# SoC_GPIO_3_3V.net
KiCad netlist of a schematic drawn in Altium Designer
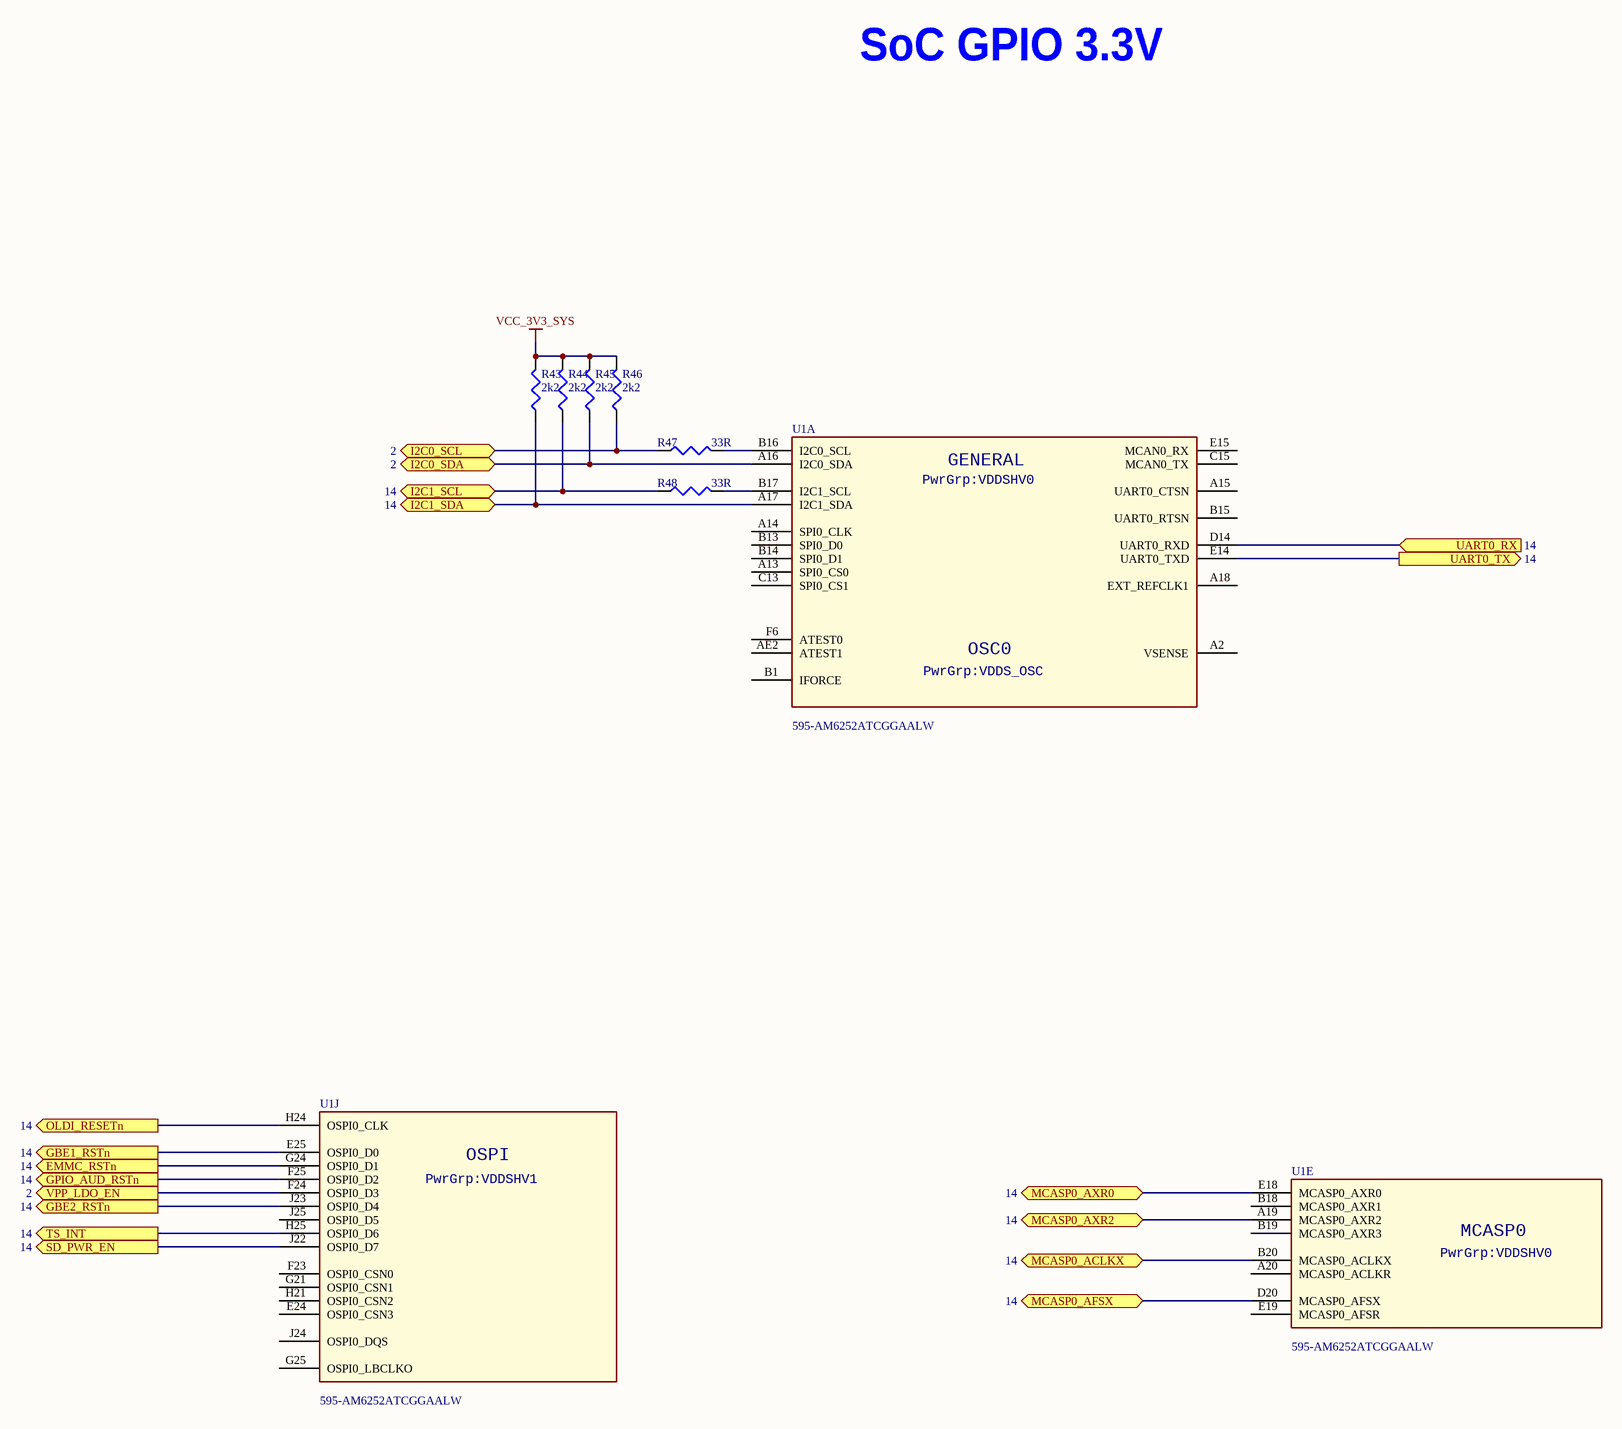
[diagram p0: SoC GPIO 3.3V.SchDoc]

(export (version "E")
  (design (tool "Eeschema 10.0.6"))
  (components
    (comp (ref "R43")
      (value "2k2")
      (footprint "R0402")
      (description "RES 2.20K OHM 1/16W 1% 0402 SMD")
      (fields
        (field (name "MANUFACTURER") "Yageo")
        (field (name "MANUFACTURER PART NUMBER") "RC0402FR-072K2L")
      )
      (libsource (lib "Schlib AM625") (part "RC0402FR-072K2L"))
    )
    (comp (ref "R44")
      (value "2k2")
      (footprint "R0402")
      (description "RES 2.20K OHM 1/16W 1% 0402 SMD")
      (fields
        (field (name "MANUFACTURER") "Yageo")
        (field (name "MANUFACTURER PART NUMBER") "RC0402FR-072K2L")
      )
      (libsource (lib "Schlib AM625") (part "RC0402FR-072K2L"))
    )
    (comp (ref "R45")
      (value "2k2")
      (footprint "R0402")
      (description "RES 2.20K OHM 1/16W 1% 0402 SMD")
      (fields
        (field (name "MANUFACTURER") "Yageo")
        (field (name "MANUFACTURER PART NUMBER") "RC0402FR-072K2L")
      )
      (libsource (lib "Schlib AM625") (part "RC0402FR-072K2L"))
    )
    (comp (ref "R46")
      (value "2k2")
      (footprint "R0402")
      (description "RES 2.20K OHM 1/16W 1% 0402 SMD")
      (fields
        (field (name "MANUFACTURER") "Yageo")
        (field (name "MANUFACTURER PART NUMBER") "RC0402FR-072K2L")
      )
      (libsource (lib "Schlib AM625") (part "RC0402FR-072K2L"))
    )
    (comp (ref "R47")
      (value "33R")
      (footprint "R0201")
      (description "RES 33 OHM 1% 1/20W 0201")
      (fields
        (field (name "MANUFACTURER") "Yageo")
        (field (name "MANUFACTURER PART NUMBER") "RC0201FR-0733RL")
      )
      (libsource (lib "Schlib AM625") (part "RC0201FR-0733RL"))
    )
    (comp (ref "R48")
      (value "33R")
      (footprint "R0201")
      (description "RES 33 OHM 1% 1/20W 0201")
      (fields
        (field (name "MANUFACTURER") "Yageo")
        (field (name "MANUFACTURER PART NUMBER") "RC0201FR-0733RL")
      )
      (libsource (lib "Schlib AM625") (part "RC0201FR-0733RL"))
    )
    (comp (ref "U1")
      (value "AM62-EVM_BGA425")
      (footprint "BGA425C50P25X25_1300X1300X89")
      (description "ARM® Cortex®-A53 Microprocessor IC Sitara™ 2 Core, 64-Bit 1.4GHz 425-FCCSP (13x13)")
      (fields
        (field (name "MANUFACTURER") "Texas Instruments")
        (field (name "MANUFACTURER PART NUMBER") "AM6252ATCGGAALW")
        (field (name "SUPPLIER PART NUMBER 1") "595-AM6252ATCGGAALW")
      )
      (libsource (lib "Schlib AM625") (part "AM62-EVM_BGA425"))
    )
  )
  (nets
    (net (code "1") (name "/EMMC_RSTn") (class "Default")
      (node (ref "U1") (pin "G24") (pinfunction "OSPI0_D1_G24") (pintype "passive"))
    )
    (net (code "2") (name "/GBE1_RSTn") (class "Default")
      (node (ref "U1") (pin "E25") (pinfunction "OSPI0_D0_E25") (pintype "passive"))
    )
    (net (code "3") (name "/GBE2_RSTn") (class "Default")
      (node (ref "U1") (pin "J23") (pinfunction "OSPI0_D4_J23") (pintype "passive"))
    )
    (net (code "4") (name "/GPIO_AUD_RSTn") (class "Default")
      (node (ref "U1") (pin "F25") (pinfunction "OSPI0_D2_F25") (pintype "passive"))
    )
    (net (code "5") (name "/I2C0_SCL") (class "Default")
      (node (ref "R46") (pin "1") (pinfunction "1_1") (pintype "passive"))
      (node (ref "R47") (pin "1") (pinfunction "1_1") (pintype "passive"))
    )
    (net (code "6") (name "/I2C0_SDA") (class "Default")
      (node (ref "R45") (pin "1") (pinfunction "1_1") (pintype "passive"))
      (node (ref "U1") (pin "A16") (pinfunction "I2C0_SDA_A16") (pintype "passive"))
    )
    (net (code "7") (name "/I2C1_SCL") (class "Default")
      (node (ref "R44") (pin "1") (pinfunction "1_1") (pintype "passive"))
      (node (ref "R48") (pin "1") (pinfunction "1_1") (pintype "passive"))
    )
    (net (code "8") (name "/I2C1_SDA") (class "Default")
      (node (ref "R43") (pin "1") (pinfunction "1_1") (pintype "passive"))
      (node (ref "U1") (pin "A17") (pinfunction "I2C1_SDA_A17") (pintype "passive"))
    )
    (net (code "9") (name "/MCASP0_ACLKX") (class "Default")
      (node (ref "U1") (pin "B20") (pinfunction "MCASP0_ACLKX_B20") (pintype "passive"))
    )
    (net (code "10") (name "/MCASP0_AFSX") (class "Default")
      (node (ref "U1") (pin "D20") (pinfunction "MCASP0_AFSX_D20") (pintype "passive"))
    )
    (net (code "11") (name "/MCASP0_AXR0") (class "Default")
      (node (ref "U1") (pin "E18") (pinfunction "MCASP0_AXR0_E18") (pintype "passive"))
    )
    (net (code "12") (name "/MCASP0_AXR2") (class "Default")
      (node (ref "U1") (pin "A19") (pinfunction "MCASP0_AXR2_A19") (pintype "passive"))
    )
    (net (code "13") (name "/OLDI_RESETn") (class "Default")
      (node (ref "U1") (pin "H24") (pinfunction "OSPI0_CLK_H24") (pintype "passive"))
    )
    (net (code "14") (name "/SD_PWR_EN") (class "Default")
      (node (ref "U1") (pin "J22") (pinfunction "OSPI0_D7_J22") (pintype "passive"))
    )
    (net (code "15") (name "/TS_INT") (class "Default")
      (node (ref "U1") (pin "H25") (pinfunction "OSPI0_D6_H25") (pintype "passive"))
    )
    (net (code "16") (name "/UART0_RX") (class "Default")
      (node (ref "U1") (pin "D14") (pinfunction "UART0_RXD_D14") (pintype "passive"))
    )
    (net (code "17") (name "/UART0_TX") (class "Default")
      (node (ref "U1") (pin "E14") (pinfunction "UART0_TXD_E14") (pintype "passive"))
    )
    (net (code "18") (name "/VPP_LDO_EN") (class "Default")
      (node (ref "U1") (pin "F24") (pinfunction "OSPI0_D3_F24") (pintype "passive"))
    )
    (net (code "19") (name "Net-(U1A-I2C0_SCL)") (class "Default")
      (node (ref "R47") (pin "2") (pinfunction "2_2") (pintype "passive"))
      (node (ref "U1") (pin "B16") (pinfunction "I2C0_SCL_B16") (pintype "passive"))
    )
    (net (code "20") (name "Net-(U1A-I2C1_SCL)") (class "Default")
      (node (ref "R48") (pin "2") (pinfunction "2_2") (pintype "passive"))
      (node (ref "U1") (pin "B17") (pinfunction "I2C1_SCL_B17") (pintype "passive"))
    )
    (net (code "21") (name "VCC_3V3_SYS") (class "Default")
      (node (ref "R43") (pin "2") (pinfunction "2_2") (pintype "passive"))
      (node (ref "R44") (pin "2") (pinfunction "2_2") (pintype "passive"))
      (node (ref "R45") (pin "2") (pinfunction "2_2") (pintype "passive"))
      (node (ref "R46") (pin "2") (pinfunction "2_2") (pintype "passive"))
    )
    (net (code "22") (name "unconnected-(U1A-ATEST0-PadF6)") (class "Default")
      (node (ref "U1") (pin "F6") (pinfunction "ATEST0_F6") (pintype "passive"))
    )
    (net (code "23") (name "unconnected-(U1A-ATEST1-PadAE2)") (class "Default")
      (node (ref "U1") (pin "AE2") (pinfunction "ATEST1_AE2") (pintype "passive"))
    )
    (net (code "24") (name "unconnected-(U1A-EXT_REFCLK1-PadA18)") (class "Default")
      (node (ref "U1") (pin "A18") (pinfunction "EXT_REFCLK1_A18") (pintype "passive"))
    )
    (net (code "25") (name "unconnected-(U1A-IFORCE-PadB1)") (class "Default")
      (node (ref "U1") (pin "B1") (pinfunction "IFORCE_B1") (pintype "passive"))
    )
    (net (code "26") (name "unconnected-(U1A-MCAN0_RX-PadE15)") (class "Default")
      (node (ref "U1") (pin "E15") (pinfunction "MCAN0_RX_E15") (pintype "passive"))
    )
    (net (code "27") (name "unconnected-(U1A-MCAN0_TX-PadC15)") (class "Default")
      (node (ref "U1") (pin "C15") (pinfunction "MCAN0_TX_C15") (pintype "passive"))
    )
    (net (code "28") (name "unconnected-(U1A-SPI0_CLK-PadA14)") (class "Default")
      (node (ref "U1") (pin "A14") (pinfunction "SPI0_CLK_A14") (pintype "passive"))
    )
    (net (code "29") (name "unconnected-(U1A-SPI0_CS0-PadA13)") (class "Default")
      (node (ref "U1") (pin "A13") (pinfunction "SPI0_CS0_A13") (pintype "passive"))
    )
    (net (code "30") (name "unconnected-(U1A-SPI0_CS1-PadC13)") (class "Default")
      (node (ref "U1") (pin "C13") (pinfunction "SPI0_CS1_C13") (pintype "passive"))
    )
    (net (code "31") (name "unconnected-(U1A-SPI0_D0-PadB13)") (class "Default")
      (node (ref "U1") (pin "B13") (pinfunction "SPI0_D0_B13") (pintype "passive"))
    )
    (net (code "32") (name "unconnected-(U1A-SPI0_D1-PadB14)") (class "Default")
      (node (ref "U1") (pin "B14") (pinfunction "SPI0_D1_B14") (pintype "passive"))
    )
    (net (code "33") (name "unconnected-(U1A-UART0_CTSN-PadA15)") (class "Default")
      (node (ref "U1") (pin "A15") (pinfunction "UART0_CTSN_A15") (pintype "passive"))
    )
    (net (code "34") (name "unconnected-(U1A-UART0_RTSN-PadB15)") (class "Default")
      (node (ref "U1") (pin "B15") (pinfunction "UART0_RTSN_B15") (pintype "passive"))
    )
    (net (code "35") (name "unconnected-(U1A-VSENSE-PadA2)") (class "Default")
      (node (ref "U1") (pin "A2") (pinfunction "VSENSE_A2") (pintype "passive"))
    )
    (net (code "36") (name "unconnected-(U1E-MCASP0_ACLKR-PadA20)") (class "Default")
      (node (ref "U1") (pin "A20") (pinfunction "MCASP0_ACLKR_A20") (pintype "passive"))
    )
    (net (code "37") (name "unconnected-(U1E-MCASP0_AFSR-PadE19)") (class "Default")
      (node (ref "U1") (pin "E19") (pinfunction "MCASP0_AFSR_E19") (pintype "passive"))
    )
    (net (code "38") (name "unconnected-(U1E-MCASP0_AXR1-PadB18)") (class "Default")
      (node (ref "U1") (pin "B18") (pinfunction "MCASP0_AXR1_B18") (pintype "passive"))
    )
    (net (code "39") (name "unconnected-(U1E-MCASP0_AXR3-PadB19)") (class "Default")
      (node (ref "U1") (pin "B19") (pinfunction "MCASP0_AXR3_B19") (pintype "passive"))
    )
    (net (code "40") (name "unconnected-(U1J-OSPI0_CSN0-PadF23)") (class "Default")
      (node (ref "U1") (pin "F23") (pinfunction "OSPI0_CSN0_F23") (pintype "passive"))
    )
    (net (code "41") (name "unconnected-(U1J-OSPI0_CSN1-PadG21)") (class "Default")
      (node (ref "U1") (pin "G21") (pinfunction "OSPI0_CSN1_G21") (pintype "passive"))
    )
    (net (code "42") (name "unconnected-(U1J-OSPI0_CSN2-PadH21)") (class "Default")
      (node (ref "U1") (pin "H21") (pinfunction "OSPI0_CSN2_H21") (pintype "passive"))
    )
    (net (code "43") (name "unconnected-(U1J-OSPI0_CSN3-PadE24)") (class "Default")
      (node (ref "U1") (pin "E24") (pinfunction "OSPI0_CSN3_E24") (pintype "passive"))
    )
    (net (code "44") (name "unconnected-(U1J-OSPI0_D5-PadJ25)") (class "Default")
      (node (ref "U1") (pin "J25") (pinfunction "OSPI0_D5_J25") (pintype "passive"))
    )
    (net (code "45") (name "unconnected-(U1J-OSPI0_DQS-PadJ24)") (class "Default")
      (node (ref "U1") (pin "J24") (pinfunction "OSPI0_DQS_J24") (pintype "passive"))
    )
    (net (code "46") (name "unconnected-(U1J-OSPI0_LBCLKO-PadG25)") (class "Default")
      (node (ref "U1") (pin "G25") (pinfunction "OSPI0_LBCLKO_G25") (pintype "passive"))
    )
  )
)
